# Sheet_Soldering_Iron.net
KiCad netlist of a schematic drawn in Altium Designer
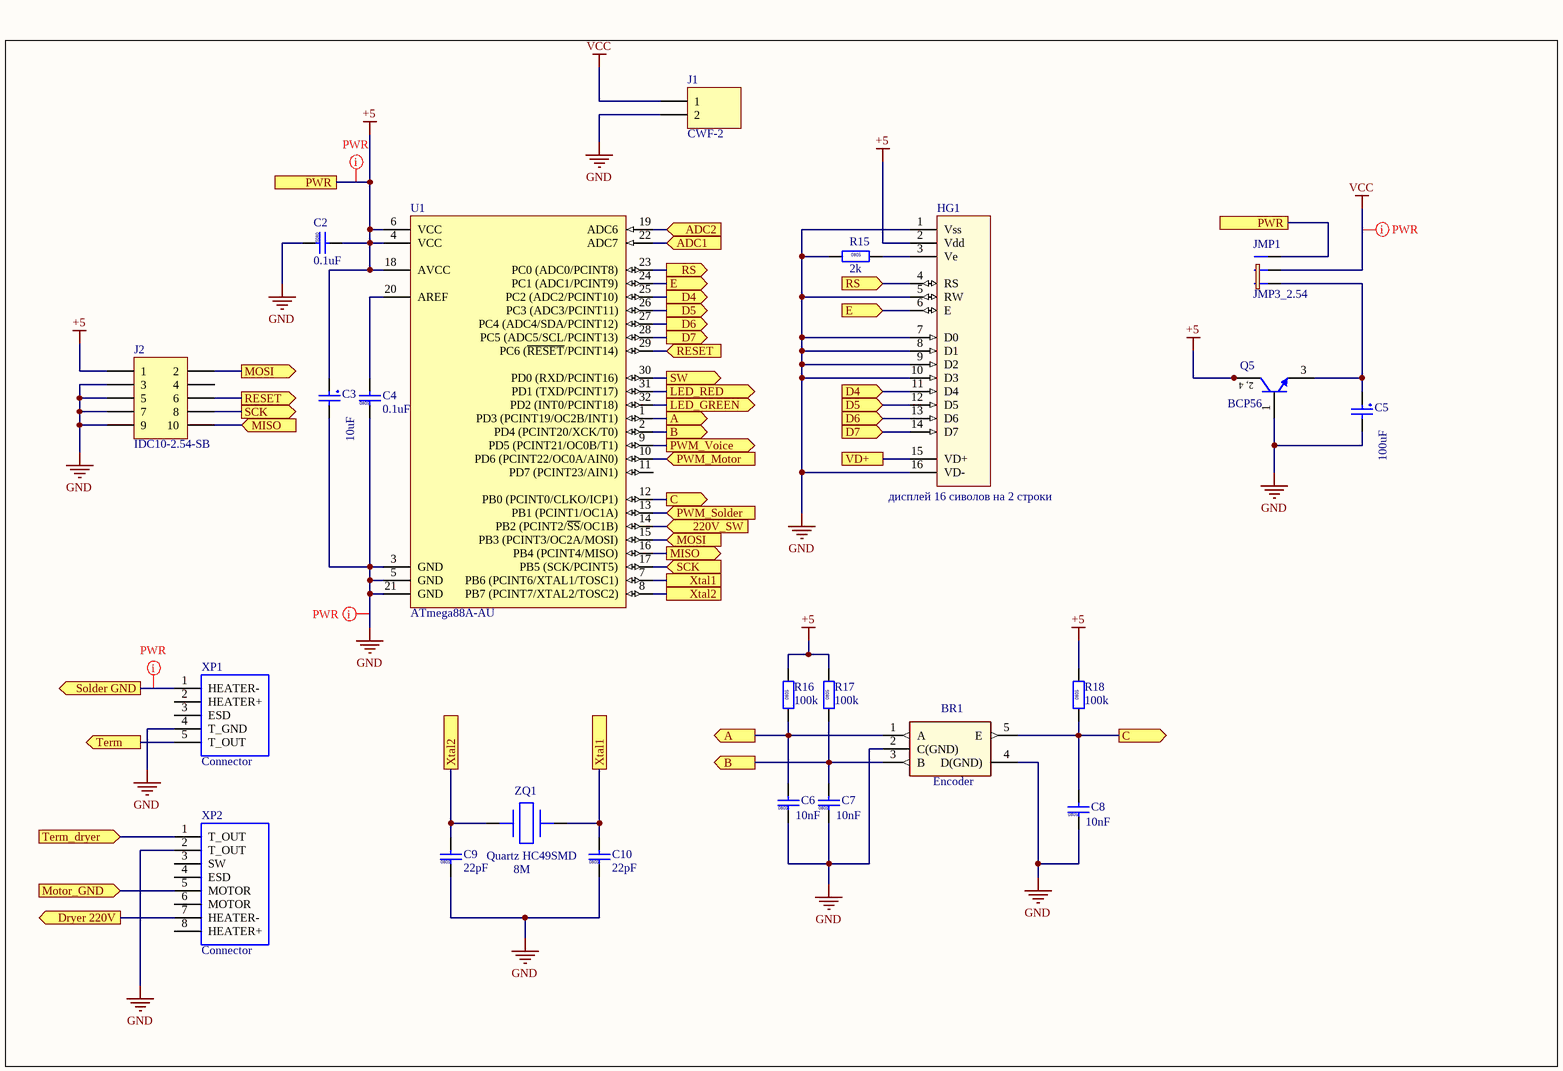
[diagram p0: Sheet_Soldering_Iron.SchDoc]

(export (version "E")
  (design (tool "Eeschema 10.0.6"))
  (components
    (comp (ref "BR1")
      (value "Encoder")
      (footprint "PCBComponent_1")
      (description "Энкодер с кнопкой")
      (libsource (lib "EC11") (part "EC11"))
    )
    (comp (ref "C2")
      (value "0.1uF")
      (footprint "CAPC2012-0805M")
      (description "Capacitor 0805")
      (fields (field (name "Comment") "CAPC_0805"))
      (libsource (lib "Passive") (part "CAPC_0805"))
    )
    (comp (ref "C3")
      (value "10uF")
      (footprint "ECAP511")
      (description "Capacitor electrolytic 2.5 mm pitch, 5*11 body")
      (fields (field (name "Comment") "ECAP-511"))
      (libsource (lib "Passive") (part "ECAP-511"))
    )
    (comp (ref "C4")
      (value "0.1uF")
      (footprint "CAPC2012-0805M")
      (description "Capacitor 0805")
      (fields (field (name "Comment") "CAPC_0805"))
      (libsource (lib "Passive") (part "CAPC_0805"))
    )
    (comp (ref "C5")
      (value "100uF")
      (footprint "ECAP511")
      (description "Capacitor electrolytic 2.5 mm pitch, 5*11 body")
      (fields (field (name "Comment") "ECAP-511"))
      (libsource (lib "Passive") (part "ECAP-511"))
    )
    (comp (ref "C6")
      (value "10nF")
      (footprint "CAPC2012-0805M")
      (description "Capacitor 0805")
      (fields (field (name "Comment") "CAPC_0805"))
      (libsource (lib "Passive") (part "CAPC_0805"))
    )
    (comp (ref "C7")
      (value "10nF")
      (footprint "CAPC2012-0805M")
      (description "Capacitor 0805")
      (fields (field (name "Comment") "CAPC_0805"))
      (libsource (lib "Passive") (part "CAPC_0805"))
    )
    (comp (ref "C8")
      (value "10nF")
      (footprint "CAPC2012-0805M")
      (description "Capacitor 0805")
      (fields (field (name "Comment") "CAPC_0805"))
      (libsource (lib "Passive") (part "CAPC_0805"))
    )
    (comp (ref "C9")
      (value "22pF")
      (footprint "CAPC2012-0805M")
      (description "Capacitor 0805")
      (fields (field (name "Comment") "CAPC_0805"))
      (libsource (lib "Passive") (part "CAPC_0805"))
    )
    (comp (ref "C10")
      (value "22pF")
      (footprint "CAPC2012-0805M")
      (description "Capacitor 0805")
      (fields (field (name "Comment") "CAPC_0805"))
      (libsource (lib "Passive") (part "CAPC_0805"))
    )
    (comp (ref "HG1")
      (value "дисплей 16 сиволов на 2 строки")
      (footprint "PCBComponent_1")
      (libsource (lib "LCD1602") (part "LCD1602"))
    )
    (comp (ref "J1") (value "CWF-2") (footprint "CWF-2") (libsource (lib "Connectors") (part "CWF-2")))
    (comp (ref "J2")
      (value "IDC10-2.54-SB")
      (footprint "IDC10-2.54-SB")
      (description "IDC10 2.54 mm pitch Straight, plastic Box")
      (fields (field (name "PUBLISHER") "Altium Limited"))
      (libsource (lib "Connectors") (part "IDC10-2.54-SB"))
    )
    (comp (ref "JMP1")
      (value "JMP3_2.54")
      (footprint "JMP3_2.54")
      (description "2.54mm 3-pin \"switching\" jumper")
      (libsource (lib "Connectors") (part "JMP3_2.54"))
    )
    (comp (ref "Q5")
      (value "BCP56")
      (footprint "SOT223_N")
      (description "NPN Medium Power Transistor")
      (fields (field (name "PUBLISHER") "Altium Limited"))
      (libsource (lib "Discrete") (part "BCP56"))
    )
    (comp (ref "R15")
      (value "2k")
      (footprint "RESC2012-0805M")
      (description "Resistor 0805")
      (fields (field (name "Comment") "RESC_0805_R"))
      (libsource (lib "Passive") (part "RESC_0805_R"))
    )
    (comp (ref "R16")
      (value "100k")
      (footprint "RESC2012-0805M")
      (description "Resistor 0805")
      (fields (field (name "Comment") "RESC_0805_R"))
      (libsource (lib "") (part "RESC_0805_R_1"))
    )
    (comp (ref "R17")
      (value "100k")
      (footprint "RESC2012-0805M")
      (description "Resistor 0805")
      (fields (field (name "Comment") "RESC_0805_R"))
      (libsource (lib "") (part "RESC_0805_R_1"))
    )
    (comp (ref "R18")
      (value "100k")
      (footprint "RESC2012-0805M")
      (description "Resistor 0805")
      (fields (field (name "Comment") "RESC_0805_R"))
      (libsource (lib "") (part "RESC_0805_R_1"))
    )
    (comp (ref "U1")
      (value "ATmega88A-AU")
      (footprint "32A_N")
      (fields (field (name "PUBLISHER") "Altium Limited"))
      (libsource (lib "Atmel Microcontroller 8-Bit megaAVR") (part "ATmega88A-AU"))
    )
    (comp (ref "XP1")
      (value "Connector")
      (footprint "PCBComponent_1")
      (description "Разъём с 5 контактами типа мама")
      (libsource (lib "GX16-5") (part "GX16-5"))
    )
    (comp (ref "XP2")
      (value "Connector")
      (footprint "PCBComponent_1")
      (description "Разъём с 8 контактами типа мама")
      (libsource (lib "GX16-8") (part "GX16-8"))
    )
    (comp (ref "ZQ1")
      (value "Quartz HC49SMD")
      (footprint "HC-49SMD")
      (fields (field (name "ALTIUM_VALUE") "8M"))
      (libsource (lib "Passive") (part "Quartz HC49SMD"))
    )
  )
  (nets
    (net (code "1") (name "+5") (class "Default")
      (node (ref "C2") (pin "2") (pinfunction "2_2") (pintype "passive"))
      (node (ref "C3") (pin "1") (pinfunction "1_1") (pintype "passive"))
      (node (ref "HG1") (pin "2") (pinfunction "Vdd_2") (pintype "power_in"))
      (node (ref "J2") (pin "1") (pinfunction "1_1") (pintype "passive"))
      (node (ref "JMP1") (pin "3") (pinfunction "3_3") (pintype "power_in"))
      (node (ref "Q5") (pin "2") (pinfunction "C_2") (pintype "passive"))
      (node (ref "Q5") (pin "4") (pinfunction "C_4") (pintype "passive"))
      (node (ref "R16") (pin "2") (pinfunction "2_2") (pintype "passive"))
      (node (ref "R17") (pin "2") (pinfunction "2_2") (pintype "passive"))
      (node (ref "R18") (pin "2") (pinfunction "2_2") (pintype "passive"))
      (node (ref "U1") (pin "18") (pinfunction "AVCC_18") (pintype "power_in"))
      (node (ref "U1") (pin "4") (pinfunction "VCC_4") (pintype "power_in"))
      (node (ref "U1") (pin "6") (pinfunction "VCC_6") (pintype "power_in"))
    )
    (net (code "2") (name "/220V_SW") (class "Default")
      (node (ref "U1") (pin "14") (pinfunction "PB2_(PCINT2/~{SS}/OC1B)_14") (pintype "bidirectional"))
    )
    (net (code "3") (name "/A") (class "Default")
      (node (ref "BR1") (pin "1") (pinfunction "A_1") (pintype "output"))
      (node (ref "C6") (pin "2") (pinfunction "2_2") (pintype "passive"))
      (node (ref "R16") (pin "1") (pinfunction "1_1") (pintype "passive"))
      (node (ref "U1") (pin "1") (pinfunction "PD3_(PCINT19/OC2B/INT1)_1") (pintype "bidirectional"))
    )
    (net (code "4") (name "/ADC1") (class "Default")
      (node (ref "U1") (pin "22") (pinfunction "ADC7_22") (pintype "input"))
    )
    (net (code "5") (name "/ADC2") (class "Default")
      (node (ref "U1") (pin "19") (pinfunction "ADC6_19") (pintype "input"))
    )
    (net (code "6") (name "/B") (class "Default")
      (node (ref "BR1") (pin "3") (pinfunction "B_3") (pintype "output"))
      (node (ref "C7") (pin "2") (pinfunction "2_2") (pintype "passive"))
      (node (ref "R17") (pin "1") (pinfunction "1_1") (pintype "passive"))
      (node (ref "U1") (pin "2") (pinfunction "PD4_(PCINT20/XCK/T0)_2") (pintype "bidirectional"))
    )
    (net (code "7") (name "/C") (class "Default")
      (node (ref "BR1") (pin "5") (pinfunction "E_5") (pintype "output"))
      (node (ref "C8") (pin "2") (pinfunction "2_2") (pintype "passive"))
      (node (ref "R18") (pin "1") (pinfunction "1_1") (pintype "passive"))
      (node (ref "U1") (pin "12") (pinfunction "PB0_(PCINT0/CLKO/ICP1)_12") (pintype "bidirectional"))
    )
    (net (code "8") (name "/D4") (class "Default")
      (node (ref "HG1") (pin "11") (pinfunction "D4_11") (pintype "input"))
      (node (ref "U1") (pin "25") (pinfunction "PC2_(ADC2/PCINT10)_25") (pintype "bidirectional"))
    )
    (net (code "9") (name "/D5") (class "Default")
      (node (ref "HG1") (pin "12") (pinfunction "D5_12") (pintype "input"))
      (node (ref "U1") (pin "26") (pinfunction "PC3_(ADC3/PCINT11)_26") (pintype "bidirectional"))
    )
    (net (code "10") (name "/D6") (class "Default")
      (node (ref "HG1") (pin "13") (pinfunction "D6_13") (pintype "input"))
      (node (ref "U1") (pin "27") (pinfunction "PC4_(ADC4/SDA/PCINT12)_27") (pintype "bidirectional"))
    )
    (net (code "11") (name "/D7") (class "Default")
      (node (ref "HG1") (pin "14") (pinfunction "D7_14") (pintype "input"))
      (node (ref "U1") (pin "28") (pinfunction "PC5_(ADC5/SCL/PCINT13)_28") (pintype "bidirectional"))
    )
    (net (code "12") (name "/Dryer 220V") (class "Default")
      (node (ref "XP2") (pin "7") (pinfunction "HEATER-_7") (pintype "passive"))
    )
    (net (code "13") (name "/E") (class "Default")
      (node (ref "HG1") (pin "6") (pinfunction "E_6") (pintype "bidirectional"))
      (node (ref "U1") (pin "24") (pinfunction "PC1_(ADC1/PCINT9)_24") (pintype "bidirectional"))
    )
    (net (code "14") (name "/LED_GREEN") (class "Default")
      (node (ref "U1") (pin "32") (pinfunction "PD2_(INT0/PCINT18)_32") (pintype "bidirectional"))
    )
    (net (code "15") (name "/LED_RED") (class "Default")
      (node (ref "U1") (pin "31") (pinfunction "PD1_(TXD/PCINT17)_31") (pintype "bidirectional"))
    )
    (net (code "16") (name "/MISO") (class "Default")
      (node (ref "J2") (pin "10") (pinfunction "10_10") (pintype "passive"))
      (node (ref "U1") (pin "16") (pinfunction "PB4_(PCINT4/MISO)_16") (pintype "bidirectional"))
    )
    (net (code "17") (name "/MOSI") (class "Default")
      (node (ref "J2") (pin "2") (pinfunction "2_2") (pintype "passive"))
      (node (ref "U1") (pin "15") (pinfunction "PB3_(PCINT3/OC2A/MOSI)_15") (pintype "bidirectional"))
    )
    (net (code "18") (name "/Motor_GND") (class "Default")
      (node (ref "XP2") (pin "5") (pinfunction "MOTOR_5") (pintype "passive"))
    )
    (net (code "19") (name "/PWM_Motor") (class "Default")
      (node (ref "U1") (pin "10") (pinfunction "PD6_(PCINT22/OC0A/AIN0)_10") (pintype "bidirectional"))
    )
    (net (code "20") (name "/PWM_Solder") (class "Default")
      (node (ref "U1") (pin "13") (pinfunction "PB1_(PCINT1/OC1A)_13") (pintype "bidirectional"))
    )
    (net (code "21") (name "/PWM_Voice") (class "Default")
      (node (ref "U1") (pin "9") (pinfunction "PD5_(PCINT21/OC0B/T1)_9") (pintype "bidirectional"))
    )
    (net (code "22") (name "/RESET") (class "Default")
      (node (ref "J2") (pin "6") (pinfunction "6_6") (pintype "passive"))
      (node (ref "U1") (pin "29") (pinfunction "PC6_(~{RESET}/PCINT14)_29") (pintype "bidirectional"))
    )
    (net (code "23") (name "/RS") (class "Default")
      (node (ref "HG1") (pin "4") (pinfunction "RS_4") (pintype "bidirectional"))
      (node (ref "U1") (pin "23") (pinfunction "PC0_(ADC0/PCINT8)_23") (pintype "bidirectional"))
    )
    (net (code "24") (name "/SCK") (class "Default")
      (node (ref "J2") (pin "8") (pinfunction "8_8") (pintype "passive"))
      (node (ref "U1") (pin "17") (pinfunction "PB5_(SCK/PCINT5)_17") (pintype "bidirectional"))
    )
    (net (code "25") (name "/SW") (class "Default")
      (node (ref "U1") (pin "30") (pinfunction "PD0_(RXD/PCINT16)_30") (pintype "bidirectional"))
    )
    (net (code "26") (name "/Solder GND") (class "Default")
      (node (ref "XP1") (pin "1") (pinfunction "HEATER-_1") (pintype "passive"))
    )
    (net (code "27") (name "/Term") (class "Default")
      (node (ref "XP1") (pin "5") (pinfunction "T_OUT_5") (pintype "passive"))
    )
    (net (code "28") (name "/Term_dryer") (class "Default")
      (node (ref "XP2") (pin "1") (pinfunction "T_OUT_1") (pintype "passive"))
    )
    (net (code "29") (name "/VD+") (class "Default")
      (node (ref "HG1") (pin "15") (pinfunction "VD+_15") (pintype "power_in"))
    )
    (net (code "30") (name "/Xtal1") (class "Default")
      (node (ref "C10") (pin "2") (pinfunction "2_2") (pintype "passive"))
      (node (ref "U1") (pin "7") (pinfunction "PB6_(PCINT6/XTAL1/TOSC1)_7") (pintype "bidirectional"))
      (node (ref "ZQ1") (pin "2") (pinfunction "2_2") (pintype "passive"))
    )
    (net (code "31") (name "/Xtal2") (class "Default")
      (node (ref "C9") (pin "2") (pinfunction "2_2") (pintype "passive"))
      (node (ref "U1") (pin "8") (pinfunction "PB7_(PCINT7/XTAL2/TOSC2)_8") (pintype "bidirectional"))
      (node (ref "ZQ1") (pin "1") (pinfunction "1_1") (pintype "passive"))
    )
    (net (code "32") (name "GND") (class "Default")
      (node (ref "BR1") (pin "2") (pinfunction "C(GND)_2") (pintype "power_in"))
      (node (ref "BR1") (pin "4") (pinfunction "D(GND)_4") (pintype "power_in"))
      (node (ref "C10") (pin "1") (pinfunction "1_1") (pintype "passive"))
      (node (ref "C2") (pin "1") (pinfunction "1_1") (pintype "passive"))
      (node (ref "C3") (pin "2") (pinfunction "2_2") (pintype "passive"))
      (node (ref "C4") (pin "1") (pinfunction "1_1") (pintype "passive"))
      (node (ref "C5") (pin "2") (pinfunction "2_2") (pintype "passive"))
      (node (ref "C6") (pin "1") (pinfunction "1_1") (pintype "passive"))
      (node (ref "C7") (pin "1") (pinfunction "1_1") (pintype "passive"))
      (node (ref "C8") (pin "1") (pinfunction "1_1") (pintype "passive"))
      (node (ref "C9") (pin "1") (pinfunction "1_1") (pintype "passive"))
      (node (ref "HG1") (pin "1") (pinfunction "Vss_1") (pintype "power_in"))
      (node (ref "HG1") (pin "10") (pinfunction "D3_10") (pintype "input"))
      (node (ref "HG1") (pin "16") (pinfunction "VD-_16") (pintype "power_in"))
      (node (ref "HG1") (pin "5") (pinfunction "RW_5") (pintype "bidirectional"))
      (node (ref "HG1") (pin "7") (pinfunction "D0_7") (pintype "input"))
      (node (ref "HG1") (pin "8") (pinfunction "D1_8") (pintype "input"))
      (node (ref "HG1") (pin "9") (pinfunction "D2_9") (pintype "input"))
      (node (ref "J1") (pin "2") (pinfunction "2_2") (pintype "passive"))
      (node (ref "J2") (pin "3") (pinfunction "3_3") (pintype "passive"))
      (node (ref "J2") (pin "5") (pinfunction "5_5") (pintype "passive"))
      (node (ref "J2") (pin "7") (pinfunction "7_7") (pintype "passive"))
      (node (ref "J2") (pin "9") (pinfunction "9_9") (pintype "passive"))
      (node (ref "Q5") (pin "1") (pinfunction "B_1") (pintype "passive"))
      (node (ref "R15") (pin "1") (pinfunction "1_1") (pintype "passive"))
      (node (ref "U1") (pin "21") (pinfunction "GND_21") (pintype "power_in"))
      (node (ref "U1") (pin "3") (pinfunction "GND_3") (pintype "power_in"))
      (node (ref "U1") (pin "5") (pinfunction "GND_5") (pintype "power_in"))
      (node (ref "XP1") (pin "4") (pinfunction "T_GND_4") (pintype "passive"))
      (node (ref "XP2") (pin "2") (pinfunction "T_OUT_2") (pintype "passive"))
    )
    (net (code "33") (name "Net-(HG1-Ve)") (class "Default")
      (node (ref "HG1") (pin "3") (pinfunction "Ve_3") (pintype "power_in"))
      (node (ref "R15") (pin "2") (pinfunction "2_2") (pintype "passive"))
    )
    (net (code "34") (name "Net-(Q5-E)") (class "Default")
      (node (ref "C5") (pin "1") (pinfunction "1_1") (pintype "passive"))
      (node (ref "JMP1") (pin "1") (pinfunction "1_1") (pintype "power_in"))
      (node (ref "Q5") (pin "3") (pinfunction "E_3") (pintype "passive"))
    )
    (net (code "35") (name "Net-(U1-AREF)") (class "Default")
      (node (ref "C4") (pin "2") (pinfunction "2_2") (pintype "passive"))
      (node (ref "U1") (pin "20") (pinfunction "AREF_20") (pintype "passive"))
    )
    (net (code "36") (name "VCC") (class "Default")
      (node (ref "J1") (pin "1") (pinfunction "1_1") (pintype "passive"))
      (node (ref "JMP1") (pin "2") (pinfunction "2_2") (pintype "power_in"))
    )
    (net (code "37") (name "unconnected-(J2-Pad4)") (class "Default")
      (node (ref "J2") (pin "4") (pinfunction "4_4") (pintype "passive"))
    )
    (net (code "38") (name "unconnected-(U1-PD7_(PCINT23{slash}AIN1)-Pad11)") (class "Default")
      (node (ref "U1") (pin "11") (pinfunction "PD7_(PCINT23/AIN1)_11") (pintype "bidirectional"))
    )
    (net (code "39") (name "unconnected-(XP1-ESD-Pad3)") (class "Default")
      (node (ref "XP1") (pin "3") (pinfunction "ESD_3") (pintype "passive"))
    )
    (net (code "40") (name "unconnected-(XP1-HEATER+-Pad2)") (class "Default")
      (node (ref "XP1") (pin "2") (pinfunction "HEATER+_2") (pintype "passive"))
    )
    (net (code "41") (name "unconnected-(XP2-ESD-Pad4)") (class "Default")
      (node (ref "XP2") (pin "4") (pinfunction "ESD_4") (pintype "passive"))
    )
    (net (code "42") (name "unconnected-(XP2-HEATER+-Pad8)") (class "Default")
      (node (ref "XP2") (pin "8") (pinfunction "HEATER+_8") (pintype "passive"))
    )
    (net (code "43") (name "unconnected-(XP2-MOTOR-Pad6)") (class "Default")
      (node (ref "XP2") (pin "6") (pinfunction "MOTOR_6") (pintype "passive"))
    )
    (net (code "44") (name "unconnected-(XP2-SW-Pad3)") (class "Default")
      (node (ref "XP2") (pin "3") (pinfunction "SW_3") (pintype "passive"))
    )
  )
)
